# 464342_21-005_3_1.net
KiCad netlist of a schematic drawn in Altium Designer
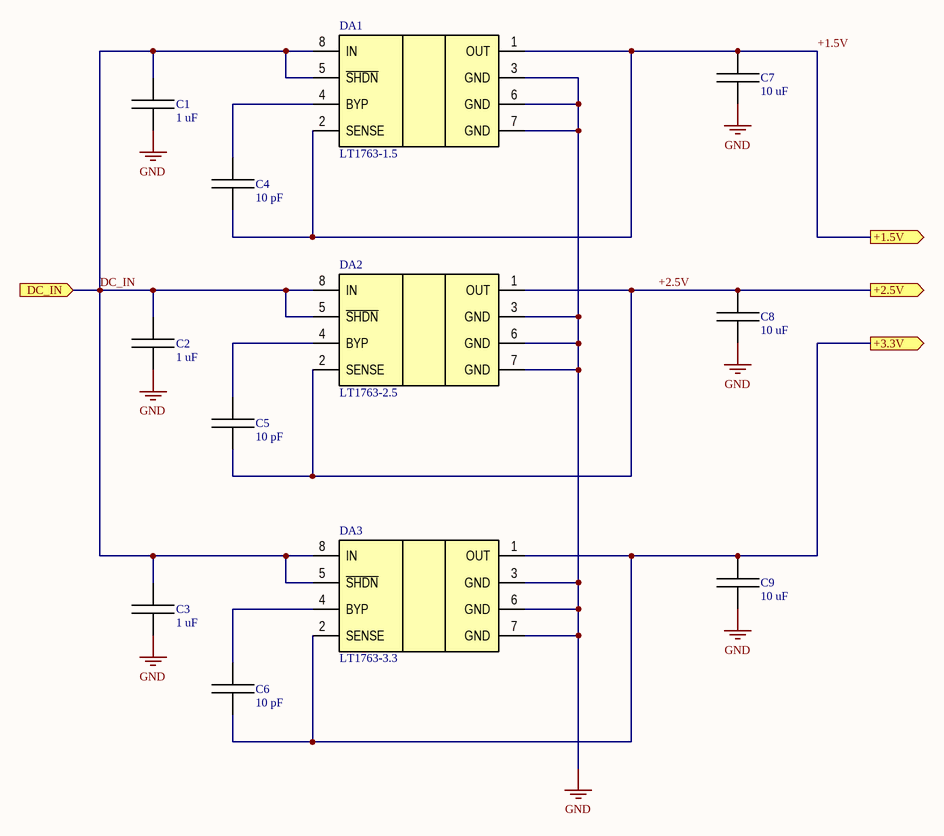
[diagram p0: МПСУ.464342.21-005 Э3 Лист1.SchDoc]

(export (version "E")
  (design (tool "Eeschema 10.0.6"))
  (components
    (comp (ref "C1")
      (value "1 uF")
      (footprint "CAPC160X80X90L30N")
      (description "Capacitor, generic")
      (libsource (lib "Discrete") (part "Capacitor"))
    )
    (comp (ref "C2")
      (value "1 uF")
      (footprint "CAPC160X80X90L30N")
      (description "Capacitor, generic")
      (libsource (lib "Discrete") (part "Capacitor"))
    )
    (comp (ref "C3")
      (value "1 uF")
      (footprint "CAPC160X80X90L30N")
      (description "Capacitor, generic")
      (libsource (lib "Discrete") (part "Capacitor"))
    )
    (comp (ref "C4")
      (value "10 pF")
      (footprint "CAPC160X80X90L30N")
      (description "Capacitor, generic")
      (libsource (lib "Discrete") (part "Capacitor"))
    )
    (comp (ref "C5")
      (value "10 pF")
      (footprint "CAPC160X80X90L30N")
      (description "Capacitor, generic")
      (libsource (lib "Discrete") (part "Capacitor"))
    )
    (comp (ref "C6")
      (value "10 pF")
      (footprint "CAPC160X80X90L30N")
      (description "Capacitor, generic")
      (libsource (lib "Discrete") (part "Capacitor"))
    )
    (comp (ref "C7")
      (value "10 uF")
      (footprint "CAPC160X80X90L30N")
      (description "Capacitor, generic")
      (libsource (lib "Discrete") (part "Capacitor"))
    )
    (comp (ref "C8")
      (value "10 uF")
      (footprint "CAPC160X80X90L30N")
      (description "Capacitor, generic")
      (libsource (lib "Discrete") (part "Capacitor"))
    )
    (comp (ref "C9")
      (value "10 uF")
      (footprint "CAPC160X80X90L30N")
      (description "Capacitor, generic")
      (libsource (lib "Discrete") (part "Capacitor"))
    )
    (comp (ref "DA1")
      (value "LT1763-1.5")
      (footprint "SOIC8P127_490X600X175L83X41N")
      (description "Micropower DC/DC Converters in SOIC8")
      (fields (field (name "MANUFACTURER") "Analog Devices"))
      (libsource (lib "PowerMangment") (part "LT1763"))
    )
    (comp (ref "DA2")
      (value "LT1763-2.5")
      (footprint "SOIC8P127_490X600X175L83X41N")
      (description "Micropower DC/DC Converters in SOIC8")
      (fields (field (name "MANUFACTURER") "Analog Devices"))
      (libsource (lib "PowerMangment") (part "LT1763"))
    )
    (comp (ref "DA3")
      (value "LT1763-3.3")
      (footprint "SOIC8P127_490X600X175L83X41N")
      (description "Micropower DC/DC Converters in SOIC8")
      (fields (field (name "MANUFACTURER") "Analog Devices"))
      (libsource (lib "PowerMangment") (part "LT1763"))
    )
  )
  (nets
    (net (code "1") (name "/+1.5V") (class "Default")
      (node (ref "C4") (pin "1") (pinfunction "1_1") (pintype "passive"))
      (node (ref "C7") (pin "2") (pinfunction "2_2") (pintype "passive"))
      (node (ref "DA1") (pin "1") (pinfunction "OUT_1") (pintype "passive"))
      (node (ref "DA1") (pin "2") (pinfunction "SENSE_2") (pintype "passive"))
    )
    (net (code "2") (name "/+2.5V") (class "Default")
      (node (ref "C5") (pin "1") (pinfunction "1_1") (pintype "passive"))
      (node (ref "C8") (pin "2") (pinfunction "2_2") (pintype "passive"))
      (node (ref "DA2") (pin "1") (pinfunction "OUT_1") (pintype "passive"))
      (node (ref "DA2") (pin "2") (pinfunction "SENSE_2") (pintype "passive"))
    )
    (net (code "3") (name "/+3.3V") (class "Default")
      (node (ref "C6") (pin "1") (pinfunction "1_1") (pintype "passive"))
      (node (ref "C9") (pin "2") (pinfunction "2_2") (pintype "passive"))
      (node (ref "DA3") (pin "1") (pinfunction "OUT_1") (pintype "passive"))
      (node (ref "DA3") (pin "2") (pinfunction "SENSE_2") (pintype "passive"))
    )
    (net (code "4") (name "/DC_IN") (class "Default")
      (node (ref "C1") (pin "2") (pinfunction "2_2") (pintype "passive"))
      (node (ref "C2") (pin "2") (pinfunction "2_2") (pintype "passive"))
      (node (ref "C3") (pin "2") (pinfunction "2_2") (pintype "passive"))
      (node (ref "DA1") (pin "5") (pinfunction "~{SHDN}_5") (pintype "passive"))
      (node (ref "DA1") (pin "8") (pinfunction "IN_8") (pintype "passive"))
      (node (ref "DA2") (pin "5") (pinfunction "~{SHDN}_5") (pintype "passive"))
      (node (ref "DA2") (pin "8") (pinfunction "IN_8") (pintype "passive"))
      (node (ref "DA3") (pin "5") (pinfunction "~{SHDN}_5") (pintype "passive"))
      (node (ref "DA3") (pin "8") (pinfunction "IN_8") (pintype "passive"))
    )
    (net (code "5") (name "GND") (class "Default")
      (node (ref "C1") (pin "1") (pinfunction "1_1") (pintype "passive"))
      (node (ref "C2") (pin "1") (pinfunction "1_1") (pintype "passive"))
      (node (ref "C3") (pin "1") (pinfunction "1_1") (pintype "passive"))
      (node (ref "C7") (pin "1") (pinfunction "1_1") (pintype "passive"))
      (node (ref "C8") (pin "1") (pinfunction "1_1") (pintype "passive"))
      (node (ref "C9") (pin "1") (pinfunction "1_1") (pintype "passive"))
      (node (ref "DA1") (pin "3") (pinfunction "GND_3") (pintype "passive"))
      (node (ref "DA1") (pin "6") (pinfunction "GND_6") (pintype "passive"))
      (node (ref "DA1") (pin "7") (pinfunction "GND_7") (pintype "passive"))
      (node (ref "DA2") (pin "3") (pinfunction "GND_3") (pintype "passive"))
      (node (ref "DA2") (pin "6") (pinfunction "GND_6") (pintype "passive"))
      (node (ref "DA2") (pin "7") (pinfunction "GND_7") (pintype "passive"))
      (node (ref "DA3") (pin "3") (pinfunction "GND_3") (pintype "passive"))
      (node (ref "DA3") (pin "6") (pinfunction "GND_6") (pintype "passive"))
      (node (ref "DA3") (pin "7") (pinfunction "GND_7") (pintype "passive"))
    )
    (net (code "6") (name "Net-(DA1-BYP)") (class "Default")
      (node (ref "C4") (pin "2") (pinfunction "2_2") (pintype "passive"))
      (node (ref "DA1") (pin "4") (pinfunction "BYP_4") (pintype "passive"))
    )
    (net (code "7") (name "Net-(DA2-BYP)") (class "Default")
      (node (ref "C5") (pin "2") (pinfunction "2_2") (pintype "passive"))
      (node (ref "DA2") (pin "4") (pinfunction "BYP_4") (pintype "passive"))
    )
    (net (code "8") (name "Net-(DA3-BYP)") (class "Default")
      (node (ref "C6") (pin "2") (pinfunction "2_2") (pintype "passive"))
      (node (ref "DA3") (pin "4") (pinfunction "BYP_4") (pintype "passive"))
    )
  )
)
